# waveshaper.net
KiCad netlist of a schematic drawn in EAGLE
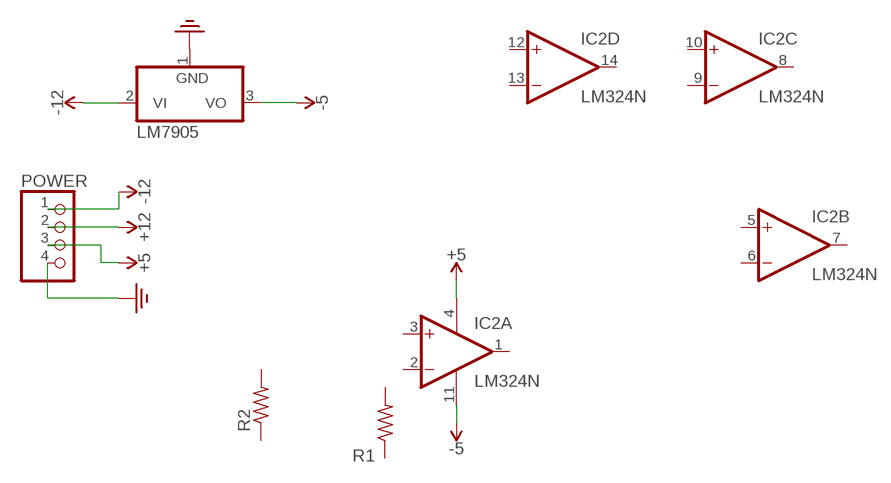
[diagram p0: schematic, sheet 1]

(export (version "E")
  (design (tool "Eeschema 10.0.6"))
  (components
    (comp (ref "IC2")
      (value "LM324N")
      (footprint "eagle-import:DIL14")
      (libsource (lib "eagle-import") (part "LM324N"))
    )
    (comp (ref "LM7905")
      (value "7905T")
      (footprint "eagle-import:TO220H")
      (libsource (lib "eagle-import") (part "79T05"))
    )
    (comp (ref "POWER")
      (value "PINHD-1X4")
      (footprint "eagle-import:1X04")
      (libsource (lib "eagle-import") (part "PINHD-1X4"))
    )
    (comp (ref "R1")
      (value "R-US_0207/12")
      (footprint "eagle-import:0207_12")
      (libsource (lib "eagle-import") (part "R-US_0207/12"))
    )
    (comp (ref "R2")
      (value "R-US_0207/12")
      (footprint "eagle-import:0207_12")
      (libsource (lib "eagle-import") (part "R-US_0207/12"))
    )
  )
  (nets
    (net (code "1") (name "+12") (class "Default")
      (node (ref "IC2") (pin "11") (pinfunction "V-_11") (pintype "power_in"))
      (node (ref "IC2") (pin "4") (pinfunction "V+_4") (pintype "power_in"))
      (node (ref "LM7905") (pin "2") (pinfunction "VI_2") (pintype "input"))
      (node (ref "LM7905") (pin "3") (pinfunction "VO_3") (pintype "passive"))
      (node (ref "POWER") (pin "1") (pinfunction "1_1") (pintype "passive"))
      (node (ref "POWER") (pin "2") (pinfunction "2_2") (pintype "passive"))
      (node (ref "POWER") (pin "3") (pinfunction "3_3") (pintype "passive"))
    )
    (net (code "2") (name "GND2") (class "Default")
      (node (ref "LM7905") (pin "1") (pinfunction "GND_1") (pintype "passive"))
      (node (ref "POWER") (pin "4") (pinfunction "4_4") (pintype "passive"))
    )
    (net (code "3") (name "unconnected-(IC2A-+IN-Pad3)") (class "Default")
      (node (ref "IC2") (pin "3") (pinfunction "+IN_3") (pintype "input"))
    )
    (net (code "4") (name "unconnected-(IC2A--IN-Pad2)") (class "Default")
      (node (ref "IC2") (pin "2") (pinfunction "-IN_2") (pintype "input"))
    )
    (net (code "5") (name "unconnected-(IC2A-OUT-Pad1)") (class "Default")
      (node (ref "IC2") (pin "1") (pinfunction "OUT_1") (pintype "output"))
    )
    (net (code "6") (name "unconnected-(IC2B-+IN-Pad5)") (class "Default")
      (node (ref "IC2") (pin "5") (pinfunction "+IN_5") (pintype "input"))
    )
    (net (code "7") (name "unconnected-(IC2B--IN-Pad6)") (class "Default")
      (node (ref "IC2") (pin "6") (pinfunction "-IN_6") (pintype "input"))
    )
    (net (code "8") (name "unconnected-(IC2B-OUT-Pad7)") (class "Default")
      (node (ref "IC2") (pin "7") (pinfunction "OUT_7") (pintype "output"))
    )
    (net (code "9") (name "unconnected-(IC2C-+IN-Pad10)") (class "Default")
      (node (ref "IC2") (pin "10") (pinfunction "+IN_10") (pintype "input"))
    )
    (net (code "10") (name "unconnected-(IC2C--IN-Pad9)") (class "Default")
      (node (ref "IC2") (pin "9") (pinfunction "-IN_9") (pintype "input"))
    )
    (net (code "11") (name "unconnected-(IC2C-OUT-Pad8)") (class "Default")
      (node (ref "IC2") (pin "8") (pinfunction "OUT_8") (pintype "output"))
    )
    (net (code "12") (name "unconnected-(IC2D-+IN-Pad12)") (class "Default")
      (node (ref "IC2") (pin "12") (pinfunction "+IN_12") (pintype "input"))
    )
    (net (code "13") (name "unconnected-(IC2D--IN-Pad13)") (class "Default")
      (node (ref "IC2") (pin "13") (pinfunction "-IN_13") (pintype "input"))
    )
    (net (code "14") (name "unconnected-(IC2D-OUT-Pad14)") (class "Default")
      (node (ref "IC2") (pin "14") (pinfunction "OUT_14") (pintype "output"))
    )
    (net (code "15") (name "unconnected-(R1-Pad1)") (class "Default")
      (node (ref "R1") (pin "1") (pinfunction "1_1") (pintype "passive"))
    )
    (net (code "16") (name "unconnected-(R1-Pad2)") (class "Default")
      (node (ref "R1") (pin "2") (pinfunction "2_2") (pintype "passive"))
    )
    (net (code "17") (name "unconnected-(R2-Pad1)") (class "Default")
      (node (ref "R2") (pin "1") (pinfunction "1_1") (pintype "passive"))
    )
    (net (code "18") (name "unconnected-(R2-Pad2)") (class "Default")
      (node (ref "R2") (pin "2") (pinfunction "2_2") (pintype "passive"))
    )
  )
)
